# modemIO_v1.net
KiCad netlist of a schematic drawn in EAGLE
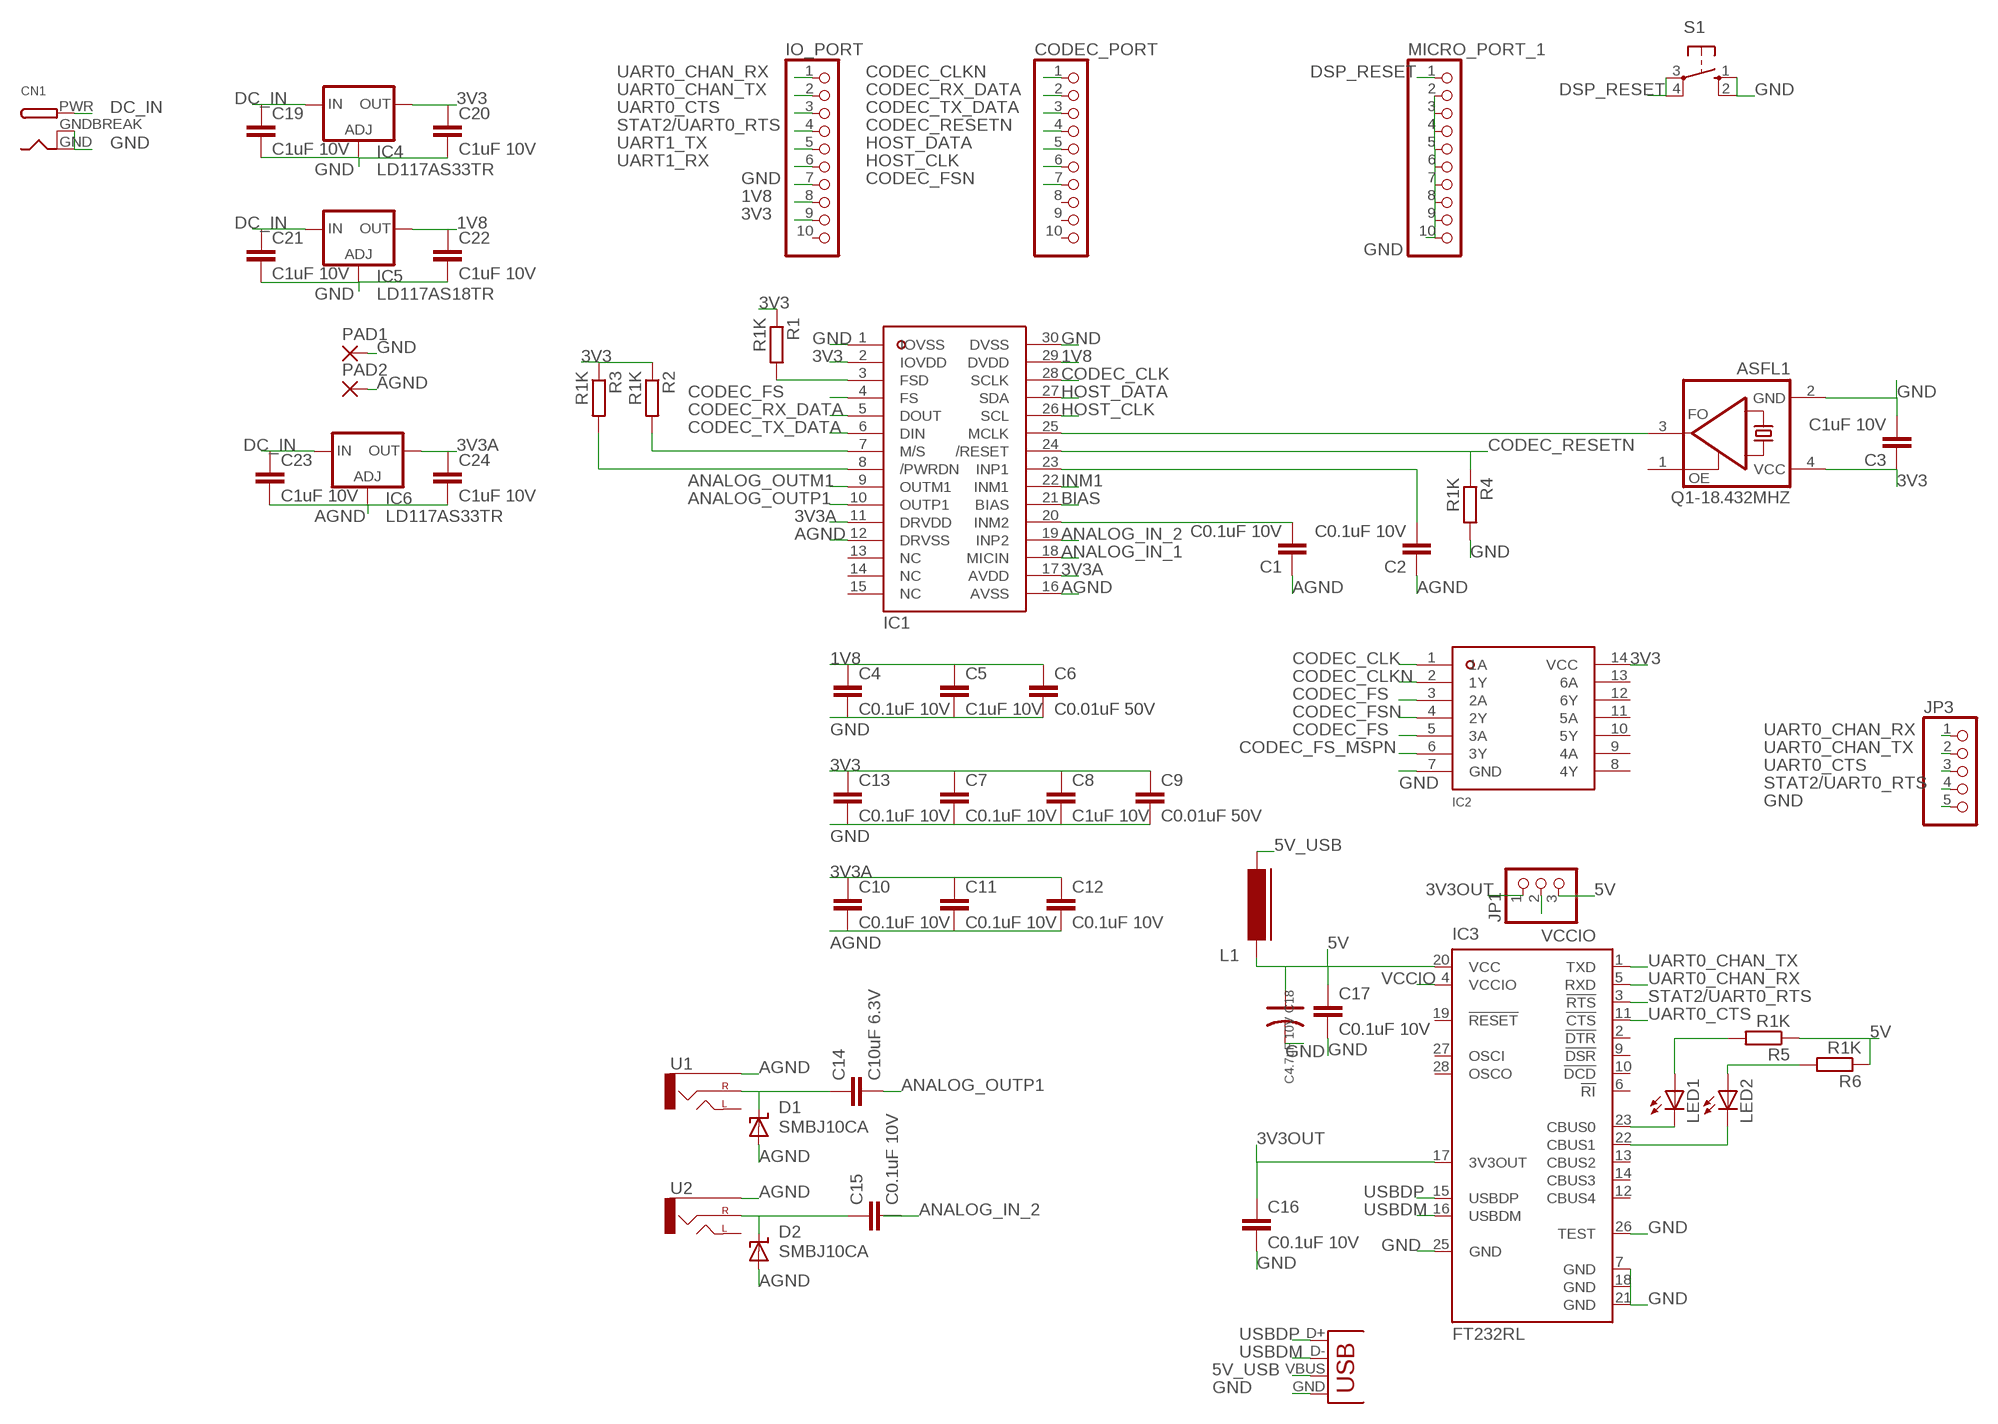
[diagram p0: schematic, sheet 1]

(export (version "E")
  (design (tool "Eeschema 10.0.6"))
  (components
    (comp (ref "C1")
      (value "C0.1uF 10V")
      (footprint "eagle-import:C0805")
      (libsource (lib "eagle-import") (part "C-EUC0805"))
    )
    (comp (ref "C2")
      (value "C0.1uF 10V")
      (footprint "eagle-import:C0805")
      (libsource (lib "eagle-import") (part "C-EUC0805"))
    )
    (comp (ref "C3")
      (value "C1uF 10V")
      (footprint "eagle-import:C0805")
      (libsource (lib "eagle-import") (part "C-EUC0805"))
    )
    (comp (ref "C4")
      (value "C0.1uF 10V")
      (footprint "eagle-import:C0805")
      (libsource (lib "eagle-import") (part "C-EUC0805"))
    )
    (comp (ref "C5")
      (value "C1uF 10V")
      (footprint "eagle-import:C0805")
      (libsource (lib "eagle-import") (part "C-EUC0805"))
    )
    (comp (ref "C6")
      (value "C0.01uF 50V")
      (footprint "eagle-import:C0805")
      (libsource (lib "eagle-import") (part "C-EUC0805"))
    )
    (comp (ref "C7")
      (value "C0.1uF 10V")
      (footprint "eagle-import:C0805")
      (libsource (lib "eagle-import") (part "C-EUC0805"))
    )
    (comp (ref "C8")
      (value "C1uF 10V")
      (footprint "eagle-import:C0805")
      (libsource (lib "eagle-import") (part "C-EUC0805"))
    )
    (comp (ref "C9")
      (value "C0.01uF 50V")
      (footprint "eagle-import:C0805")
      (libsource (lib "eagle-import") (part "C-EUC0805"))
    )
    (comp (ref "C10")
      (value "C0.1uF 10V")
      (footprint "eagle-import:C0805")
      (libsource (lib "eagle-import") (part "C-EUC0805"))
    )
    (comp (ref "C11")
      (value "C0.1uF 10V")
      (footprint "eagle-import:C0805")
      (libsource (lib "eagle-import") (part "C-EUC0805"))
    )
    (comp (ref "C12")
      (value "C0.1uF 10V")
      (footprint "eagle-import:C0805")
      (libsource (lib "eagle-import") (part "C-EUC0805"))
    )
    (comp (ref "C13")
      (value "C0.1uF 10V")
      (footprint "eagle-import:C0805")
      (libsource (lib "eagle-import") (part "C-EUC0805"))
    )
    (comp (ref "C14")
      (value "C10uF 6.3V")
      (footprint "eagle-import:C0805")
      (libsource (lib "eagle-import") (part "C-EUC0805"))
    )
    (comp (ref "C15")
      (value "C0.1uF 10V")
      (footprint "eagle-import:C0805")
      (libsource (lib "eagle-import") (part "C-EUC0805"))
    )
    (comp (ref "C16")
      (value "C0.1uF 10V")
      (footprint "eagle-import:C0805")
      (libsource (lib "eagle-import") (part "C-EUC0805"))
    )
    (comp (ref "C17")
      (value "C0.1uF 10V")
      (footprint "eagle-import:C0805")
      (libsource (lib "eagle-import") (part "C-EUC0805"))
    )
    (comp (ref "C18")
      (value "C4.7uF 10V")
      (footprint "eagle-import:AVX-C")
      (libsource (lib "eagle-import") (part "C-POLAR-C"))
    )
    (comp (ref "C19")
      (value "C1uF 10V")
      (footprint "eagle-import:C0805")
      (libsource (lib "eagle-import") (part "C-EUC0805"))
    )
    (comp (ref "C20")
      (value "C1uF 10V")
      (footprint "eagle-import:C0805")
      (libsource (lib "eagle-import") (part "C-EUC0805"))
    )
    (comp (ref "C21")
      (value "C1uF 10V")
      (footprint "eagle-import:C0805")
      (libsource (lib "eagle-import") (part "C-EUC0805"))
    )
    (comp (ref "C22")
      (value "C1uF 10V")
      (footprint "eagle-import:C0805")
      (libsource (lib "eagle-import") (part "C-EUC0805"))
    )
    (comp (ref "C23")
      (value "C1uF 10V")
      (footprint "eagle-import:C0805")
      (libsource (lib "eagle-import") (part "C-EUC0805"))
    )
    (comp (ref "C24")
      (value "C1uF 10V")
      (footprint "eagle-import:C0805")
      (libsource (lib "eagle-import") (part "C-EUC0805"))
    )
    (comp (ref "CN1")
      (value "DCBARRELPTH")
      (footprint "eagle-import:DCJACK_2MM_PTH")
      (libsource (lib "eagle-import") (part "DCBARRELPTH"))
    )
    (comp (ref "CODEC_PORT")
      (value "PINHD-1X10")
      (footprint "eagle-import:1X10")
      (libsource (lib "eagle-import") (part "PINHD-1X10"))
    )
    (comp (ref "D1")
      (value "SMBJ10CA")
      (footprint "eagle-import:SMBJ")
      (libsource (lib "eagle-import") (part "SUPPRESSOR-SMBJ"))
    )
    (comp (ref "D2")
      (value "SMBJ10CA")
      (footprint "eagle-import:SMBJ")
      (libsource (lib "eagle-import") (part "SUPPRESSOR-SMBJ"))
    )
    (comp (ref "IC1")
      (value "TLV320AIC14R-PDSO-G30")
      (footprint "eagle-import:R-PDSO-G30")
      (libsource (lib "eagle-import") (part "TLV320AIC14R-PDSO-G30"))
    )
    (comp (ref "IC2")
      (value "SN74LVC04ADRR-PDSO-G14")
      (footprint "eagle-import:R-PDSO-G14")
      (libsource (lib "eagle-import") (part "SN74LVC04ADRR-PDSO-G14"))
    )
    (comp (ref "IC3")
      (value "FT232RL")
      (footprint "eagle-import:SSOP28")
      (libsource (lib "eagle-import") (part "FT232RL"))
    )
    (comp (ref "IC4")
      (value "LD117AS33TR")
      (footprint "eagle-import:SOT223")
      (libsource (lib "eagle-import") (part "LD117A?S33TR"))
    )
    (comp (ref "IC5")
      (value "LD117AS18TR")
      (footprint "eagle-import:SOT223")
      (libsource (lib "eagle-import") (part "LD117A?S18TR"))
    )
    (comp (ref "IC6")
      (value "LD117AS33TR")
      (footprint "eagle-import:SOT223")
      (libsource (lib "eagle-import") (part "LD117A?S33TR"))
    )
    (comp (ref "IO_PORT")
      (value "PINHD-1X10")
      (footprint "eagle-import:1X10")
      (libsource (lib "eagle-import") (part "PINHD-1X10"))
    )
    (comp (ref "JP1")
      (value "PINHD-1X3")
      (footprint "eagle-import:1X03")
      (libsource (lib "eagle-import") (part "PINHD-1X3"))
    )
    (comp (ref "JP2")
      (value "USBSMD")
      (footprint "eagle-import:USB-MINIB")
      (libsource (lib "eagle-import") (part "USBSMD"))
    )
    (comp (ref "JP3")
      (value "PINHD-1X5")
      (footprint "eagle-import:1X05")
      (libsource (lib "eagle-import") (part "PINHD-1X5"))
    )
    (comp (ref "L1")
      (value "FERRITE-0603")
      (footprint "eagle-import:FB603")
      (libsource (lib "eagle-import") (part "FERRITE-0603"))
    )
    (comp (ref "LED1")
      (value "LEDCHIP-LED0805")
      (footprint "eagle-import:CHIP-LED0805")
      (libsource (lib "eagle-import") (part "LEDCHIP-LED0805"))
    )
    (comp (ref "LED2")
      (value "LEDCHIP-LED0805")
      (footprint "eagle-import:CHIP-LED0805")
      (libsource (lib "eagle-import") (part "LEDCHIP-LED0805"))
    )
    (comp (ref "MICRO_PORT_1")
      (value "PINHD-1X10")
      (footprint "eagle-import:1X10")
      (libsource (lib "eagle-import") (part "PINHD-1X10"))
    )
    (comp (ref "PAD1")
      (value "SMD2")
      (footprint "eagle-import:SMD1,27-2,54")
      (libsource (lib "eagle-import") (part "SMD2"))
    )
    (comp (ref "PAD2")
      (value "SMD2")
      (footprint "eagle-import:SMD1,27-2,54")
      (libsource (lib "eagle-import") (part "SMD2"))
    )
    (comp (ref "Q1-18.432MHZ")
      (value "ASFL1")
      (footprint "eagle-import:ASF")
      (fields (field (name "MF") "Abracon Corporation") (field (name "MPN") "ASFL1-125.000MHZ-EC-T"))
      (libsource (lib "eagle-import") (part "ASFL1"))
    )
    (comp (ref "R1")
      (value "R1K")
      (footprint "eagle-import:R0805")
      (libsource (lib "eagle-import") (part "R-EU_R0805"))
    )
    (comp (ref "R2")
      (value "R1K")
      (footprint "eagle-import:R0805")
      (libsource (lib "eagle-import") (part "R-EU_R0805"))
    )
    (comp (ref "R3")
      (value "R1K")
      (footprint "eagle-import:R0805")
      (libsource (lib "eagle-import") (part "R-EU_R0805"))
    )
    (comp (ref "R4")
      (value "R1K")
      (footprint "eagle-import:R0805")
      (libsource (lib "eagle-import") (part "R-EU_R0805"))
    )
    (comp (ref "R5")
      (value "R1K")
      (footprint "eagle-import:R0805")
      (libsource (lib "eagle-import") (part "R-EU_R0805"))
    )
    (comp (ref "R6")
      (value "R1K")
      (footprint "eagle-import:R0805")
      (libsource (lib "eagle-import") (part "R-EU_R0805"))
    )
    (comp (ref "S1")
      (value "10-XX")
      (footprint "eagle-import:B3F-10XX")
      (fields (field (name "MPN") "B3F-1000"))
      (libsource (lib "eagle-import") (part "10-XX"))
    )
    (comp (ref "U1")
      (value "AUDIO-JACKSMD2")
      (footprint "eagle-import:AUDIO-JACK-3.5MM-SMD")
      (libsource (lib "eagle-import") (part "AUDIO-JACKSMD2"))
    )
    (comp (ref "U2")
      (value "AUDIO-JACKSMD2")
      (footprint "eagle-import:AUDIO-JACK-3.5MM-SMD")
      (libsource (lib "eagle-import") (part "AUDIO-JACKSMD2"))
    )
  )
  (nets
    (net (code "1") (name "/1V8") (class "Default")
      (node (ref "C22") (pin "1") (pinfunction "1_1") (pintype "passive"))
      (node (ref "C4") (pin "1") (pinfunction "1_1") (pintype "passive"))
      (node (ref "C5") (pin "1") (pinfunction "1_1") (pintype "passive"))
      (node (ref "C6") (pin "1") (pinfunction "1_1") (pintype "passive"))
      (node (ref "IC1") (pin "29") (pinfunction "DVDD_29") (pintype "bidirectional"))
      (node (ref "IC5") (pin "4") (pinfunction "OUT_4") (pintype "passive"))
      (node (ref "IO_PORT") (pin "8") (pinfunction "8_8") (pintype "passive"))
    )
    (net (code "2") (name "/3V3") (class "Default")
      (node (ref "C13") (pin "1") (pinfunction "1_1") (pintype "passive"))
      (node (ref "C20") (pin "1") (pinfunction "1_1") (pintype "passive"))
      (node (ref "C3") (pin "1") (pinfunction "1_1") (pintype "passive"))
      (node (ref "C7") (pin "1") (pinfunction "1_1") (pintype "passive"))
      (node (ref "C8") (pin "1") (pinfunction "1_1") (pintype "passive"))
      (node (ref "C9") (pin "1") (pinfunction "1_1") (pintype "passive"))
      (node (ref "IC1") (pin "2") (pinfunction "IOVDD_2") (pintype "bidirectional"))
      (node (ref "IC2") (pin "14") (pinfunction "VCC_14") (pintype "bidirectional"))
      (node (ref "IC4") (pin "4") (pinfunction "OUT_4") (pintype "passive"))
      (node (ref "IO_PORT") (pin "9") (pinfunction "9_9") (pintype "passive"))
      (node (ref "Q1-18.432MHZ") (pin "4") (pinfunction "VCC_4") (pintype "power_in"))
      (node (ref "R1") (pin "1") (pinfunction "1_1") (pintype "passive"))
      (node (ref "R2") (pin "1") (pinfunction "1_1") (pintype "passive"))
      (node (ref "R3") (pin "1") (pinfunction "1_1") (pintype "passive"))
    )
    (net (code "3") (name "/3V3A") (class "Default")
      (node (ref "C10") (pin "1") (pinfunction "1_1") (pintype "passive"))
      (node (ref "C11") (pin "1") (pinfunction "1_1") (pintype "passive"))
      (node (ref "C12") (pin "1") (pinfunction "1_1") (pintype "passive"))
      (node (ref "C24") (pin "1") (pinfunction "1_1") (pintype "passive"))
      (node (ref "IC1") (pin "11") (pinfunction "DRVDD_11") (pintype "bidirectional"))
      (node (ref "IC1") (pin "17") (pinfunction "AVDD_17") (pintype "bidirectional"))
      (node (ref "IC6") (pin "4") (pinfunction "OUT_4") (pintype "passive"))
    )
    (net (code "4") (name "/3V3OUT") (class "Default")
      (node (ref "C16") (pin "1") (pinfunction "1_1") (pintype "passive"))
      (node (ref "IC3") (pin "17") (pinfunction "3V3OUT_17") (pintype "output"))
      (node (ref "JP1") (pin "1") (pinfunction "1_1") (pintype "passive"))
    )
    (net (code "5") (name "/5V") (class "Default")
      (node (ref "C17") (pin "1") (pinfunction "1_1") (pintype "passive"))
      (node (ref "C18") (pin "+") (pinfunction "1_+") (pintype "bidirectional"))
      (node (ref "IC3") (pin "20") (pinfunction "VCC_20") (pintype "power_in"))
      (node (ref "JP1") (pin "3") (pinfunction "3_3") (pintype "passive"))
      (node (ref "L1") (pin "1") (pinfunction "1_1") (pintype "passive"))
      (node (ref "R5") (pin "1") (pinfunction "1_1") (pintype "passive"))
      (node (ref "R6") (pin "1") (pinfunction "1_1") (pintype "passive"))
    )
    (net (code "6") (name "/5V_USB") (class "Default")
      (node (ref "JP2") (pin "VBUS") (pinfunction "VBUS_VBUS") (pintype "bidirectional"))
      (node (ref "L1") (pin "2") (pinfunction "2_2") (pintype "passive"))
    )
    (net (code "7") (name "/AGND") (class "Default")
      (node (ref "C1") (pin "1") (pinfunction "1_1") (pintype "passive"))
      (node (ref "C10") (pin "2") (pinfunction "2_2") (pintype "passive"))
      (node (ref "C11") (pin "2") (pinfunction "2_2") (pintype "passive"))
      (node (ref "C12") (pin "2") (pinfunction "2_2") (pintype "passive"))
      (node (ref "C2") (pin "1") (pinfunction "1_1") (pintype "passive"))
      (node (ref "C23") (pin "2") (pinfunction "2_2") (pintype "passive"))
      (node (ref "C24") (pin "2") (pinfunction "2_2") (pintype "passive"))
      (node (ref "D1") (pin "A") (pinfunction "A_A") (pintype "passive"))
      (node (ref "D2") (pin "A") (pinfunction "A_A") (pintype "passive"))
      (node (ref "IC1") (pin "12") (pinfunction "DRVSS_12") (pintype "bidirectional"))
      (node (ref "IC1") (pin "16") (pinfunction "AVSS_16") (pintype "bidirectional"))
      (node (ref "IC6") (pin "1") (pinfunction "ADJ_1") (pintype "input"))
      (node (ref "PAD2") (pin "1") (pinfunction "P_1") (pintype "passive"))
      (node (ref "U1") (pin "SLEEVE") (pinfunction "SLEEVE_SLEEVE") (pintype "bidirectional"))
      (node (ref "U2") (pin "SLEEVE") (pinfunction "SLEEVE_SLEEVE") (pintype "bidirectional"))
    )
    (net (code "8") (name "/ANALOG_IN_1") (class "Default")
      (node (ref "IC1") (pin "18") (pinfunction "MICIN_18") (pintype "bidirectional"))
    )
    (net (code "9") (name "/ANALOG_IN_2") (class "Default")
      (node (ref "C15") (pin "2") (pinfunction "2_2") (pintype "passive"))
      (node (ref "IC1") (pin "19") (pinfunction "INP2_19") (pintype "bidirectional"))
    )
    (net (code "10") (name "/ANALOG_OUTM1") (class "Default")
      (node (ref "IC1") (pin "9") (pinfunction "OUTM1_9") (pintype "bidirectional"))
    )
    (net (code "11") (name "/ANALOG_OUTP1") (class "Default")
      (node (ref "C14") (pin "2") (pinfunction "2_2") (pintype "passive"))
      (node (ref "IC1") (pin "10") (pinfunction "OUTP1_10") (pintype "bidirectional"))
    )
    (net (code "12") (name "/BIAS") (class "Default")
      (node (ref "IC1") (pin "21") (pinfunction "BIAS_21") (pintype "bidirectional"))
    )
    (net (code "13") (name "/CODEC_CLK") (class "Default")
      (node (ref "IC1") (pin "28") (pinfunction "SCLK_28") (pintype "bidirectional"))
      (node (ref "IC2") (pin "1") (pinfunction "1A_1") (pintype "bidirectional"))
    )
    (net (code "14") (name "/CODEC_CLKN") (class "Default")
      (node (ref "CODEC_PORT") (pin "1") (pinfunction "1_1") (pintype "passive"))
      (node (ref "IC2") (pin "2") (pinfunction "1Y_2") (pintype "bidirectional"))
    )
    (net (code "15") (name "/CODEC_FS") (class "Default")
      (node (ref "IC1") (pin "4") (pinfunction "FS_4") (pintype "bidirectional"))
      (node (ref "IC2") (pin "3") (pinfunction "2A_3") (pintype "bidirectional"))
      (node (ref "IC2") (pin "5") (pinfunction "3A_5") (pintype "bidirectional"))
    )
    (net (code "16") (name "/CODEC_FSN") (class "Default")
      (node (ref "CODEC_PORT") (pin "7") (pinfunction "7_7") (pintype "passive"))
      (node (ref "IC2") (pin "4") (pinfunction "2Y_4") (pintype "bidirectional"))
    )
    (net (code "17") (name "/CODEC_FS_MSPN") (class "Default")
      (node (ref "IC2") (pin "6") (pinfunction "3Y_6") (pintype "bidirectional"))
    )
    (net (code "18") (name "/CODEC_RESETN") (class "Default")
      (node (ref "CODEC_PORT") (pin "4") (pinfunction "4_4") (pintype "passive"))
      (node (ref "IC1") (pin "24") (pinfunction "/RESET_24") (pintype "bidirectional"))
      (node (ref "R4") (pin "1") (pinfunction "1_1") (pintype "passive"))
    )
    (net (code "19") (name "/CODEC_RX_DATA") (class "Default")
      (node (ref "CODEC_PORT") (pin "2") (pinfunction "2_2") (pintype "passive"))
      (node (ref "IC1") (pin "5") (pinfunction "DOUT_5") (pintype "bidirectional"))
    )
    (net (code "20") (name "/CODEC_TX_DATA") (class "Default")
      (node (ref "CODEC_PORT") (pin "3") (pinfunction "3_3") (pintype "passive"))
      (node (ref "IC1") (pin "6") (pinfunction "DIN_6") (pintype "bidirectional"))
    )
    (net (code "21") (name "/DC_IN") (class "Default")
      (node (ref "C19") (pin "1") (pinfunction "1_1") (pintype "passive"))
      (node (ref "C21") (pin "1") (pinfunction "1_1") (pintype "passive"))
      (node (ref "C23") (pin "1") (pinfunction "1_1") (pintype "passive"))
      (node (ref "CN1") (pin "PWR") (pinfunction "PWR_PWR") (pintype "power_in"))
      (node (ref "IC4") (pin "3") (pinfunction "IN_3") (pintype "input"))
      (node (ref "IC5") (pin "3") (pinfunction "IN_3") (pintype "input"))
      (node (ref "IC6") (pin "3") (pinfunction "IN_3") (pintype "input"))
    )
    (net (code "22") (name "/DSP_RESET") (class "Default")
      (node (ref "MICRO_PORT_1") (pin "1") (pinfunction "1_1") (pintype "passive"))
      (node (ref "S1") (pin "3") (pinfunction "P_3") (pintype "passive"))
      (node (ref "S1") (pin "4") (pinfunction "P1_4") (pintype "passive"))
    )
    (net (code "23") (name "/GND") (class "Default")
      (node (ref "C13") (pin "2") (pinfunction "2_2") (pintype "passive"))
      (node (ref "C16") (pin "2") (pinfunction "2_2") (pintype "passive"))
      (node (ref "C17") (pin "2") (pinfunction "2_2") (pintype "passive"))
      (node (ref "C18") (pin "-") (pinfunction "2_-") (pintype "bidirectional"))
      (node (ref "C19") (pin "2") (pinfunction "2_2") (pintype "passive"))
      (node (ref "C20") (pin "2") (pinfunction "2_2") (pintype "passive"))
      (node (ref "C21") (pin "2") (pinfunction "2_2") (pintype "passive"))
      (node (ref "C22") (pin "2") (pinfunction "2_2") (pintype "passive"))
      (node (ref "C3") (pin "2") (pinfunction "2_2") (pintype "passive"))
      (node (ref "C4") (pin "2") (pinfunction "2_2") (pintype "passive"))
      (node (ref "C5") (pin "2") (pinfunction "2_2") (pintype "passive"))
      (node (ref "C6") (pin "2") (pinfunction "2_2") (pintype "passive"))
      (node (ref "C7") (pin "2") (pinfunction "2_2") (pintype "passive"))
      (node (ref "C8") (pin "2") (pinfunction "2_2") (pintype "passive"))
      (node (ref "C9") (pin "2") (pinfunction "2_2") (pintype "passive"))
      (node (ref "CN1") (pin "GND") (pinfunction "GND_GND") (pintype "power_in"))
      (node (ref "CN1") (pin "GNDBREAK") (pinfunction "GNDBREAK_GNDBREAK") (pintype "power_in"))
      (node (ref "IC1") (pin "1") (pinfunction "IOVSS_1") (pintype "bidirectional"))
      (node (ref "IC1") (pin "30") (pinfunction "DVSS_30") (pintype "bidirectional"))
      (node (ref "IC2") (pin "7") (pinfunction "GND_7") (pintype "bidirectional"))
      (node (ref "IC3") (pin "18") (pinfunction "GND_18") (pintype "power_in"))
      (node (ref "IC3") (pin "21") (pinfunction "GND_21") (pintype "power_in"))
      (node (ref "IC3") (pin "25") (pinfunction "GND_25") (pintype "power_in"))
      (node (ref "IC3") (pin "26") (pinfunction "TEST_26") (pintype "input"))
      (node (ref "IC3") (pin "7") (pinfunction "GND_7") (pintype "power_in"))
      (node (ref "IC4") (pin "1") (pinfunction "ADJ_1") (pintype "input"))
      (node (ref "IC5") (pin "1") (pinfunction "ADJ_1") (pintype "input"))
      (node (ref "IO_PORT") (pin "7") (pinfunction "7_7") (pintype "passive"))
      (node (ref "JP2") (pin "GND") (pinfunction "GND_GND") (pintype "bidirectional"))
      (node (ref "JP3") (pin "5") (pinfunction "5_5") (pintype "passive"))
      (node (ref "MICRO_PORT_1") (pin "10") (pinfunction "10_10") (pintype "passive"))
      (node (ref "MICRO_PORT_1") (pin "2") (pinfunction "2_2") (pintype "passive"))
      (node (ref "MICRO_PORT_1") (pin "3") (pinfunction "3_3") (pintype "passive"))
      (node (ref "MICRO_PORT_1") (pin "4") (pinfunction "4_4") (pintype "passive"))
      (node (ref "MICRO_PORT_1") (pin "5") (pinfunction "5_5") (pintype "passive"))
      (node (ref "MICRO_PORT_1") (pin "6") (pinfunction "6_6") (pintype "passive"))
      (node (ref "MICRO_PORT_1") (pin "7") (pinfunction "7_7") (pintype "passive"))
      (node (ref "MICRO_PORT_1") (pin "8") (pinfunction "8_8") (pintype "passive"))
      (node (ref "MICRO_PORT_1") (pin "9") (pinfunction "9_9") (pintype "passive"))
      (node (ref "PAD1") (pin "1") (pinfunction "P_1") (pintype "passive"))
      (node (ref "Q1-18.432MHZ") (pin "2") (pinfunction "GND_2") (pintype "power_in"))
      (node (ref "R4") (pin "2") (pinfunction "2_2") (pintype "passive"))
      (node (ref "S1") (pin "1") (pinfunction "S_1") (pintype "passive"))
      (node (ref "S1") (pin "2") (pinfunction "S1_2") (pintype "passive"))
    )
    (net (code "24") (name "/HOST_CLK") (class "Default")
      (node (ref "CODEC_PORT") (pin "6") (pinfunction "6_6") (pintype "passive"))
      (node (ref "IC1") (pin "26") (pinfunction "SCL_26") (pintype "bidirectional"))
    )
    (net (code "25") (name "/HOST_DATA") (class "Default")
      (node (ref "CODEC_PORT") (pin "5") (pinfunction "5_5") (pintype "passive"))
      (node (ref "IC1") (pin "27") (pinfunction "SDA_27") (pintype "bidirectional"))
    )
    (net (code "26") (name "/INM1") (class "Default")
      (node (ref "IC1") (pin "22") (pinfunction "INM1_22") (pintype "bidirectional"))
    )
    (net (code "27") (name "/STAT2{slash}UART0_RTS") (class "Default")
      (node (ref "IC3") (pin "3") (pinfunction "~{RTS}_3") (pintype "output"))
      (node (ref "IO_PORT") (pin "4") (pinfunction "4_4") (pintype "passive"))
      (node (ref "JP3") (pin "4") (pinfunction "4_4") (pintype "passive"))
    )
    (net (code "28") (name "/UART0_CHAN_RX") (class "Default")
      (node (ref "IC3") (pin "5") (pinfunction "RXD_5") (pintype "input"))
      (node (ref "IO_PORT") (pin "1") (pinfunction "1_1") (pintype "passive"))
      (node (ref "JP3") (pin "1") (pinfunction "1_1") (pintype "passive"))
    )
    (net (code "29") (name "/UART0_CHAN_TX") (class "Default")
      (node (ref "IC3") (pin "1") (pinfunction "TXD_1") (pintype "output"))
      (node (ref "IO_PORT") (pin "2") (pinfunction "2_2") (pintype "passive"))
      (node (ref "JP3") (pin "2") (pinfunction "2_2") (pintype "passive"))
    )
    (net (code "30") (name "/UART0_CTS") (class "Default")
      (node (ref "IC3") (pin "11") (pinfunction "~{CTS}_11") (pintype "input"))
      (node (ref "IO_PORT") (pin "3") (pinfunction "3_3") (pintype "passive"))
      (node (ref "JP3") (pin "3") (pinfunction "3_3") (pintype "passive"))
    )
    (net (code "31") (name "/UART1_RX") (class "Default")
      (node (ref "IO_PORT") (pin "6") (pinfunction "6_6") (pintype "passive"))
    )
    (net (code "32") (name "/UART1_TX") (class "Default")
      (node (ref "IO_PORT") (pin "5") (pinfunction "5_5") (pintype "passive"))
    )
    (net (code "33") (name "/USBDM") (class "Default")
      (node (ref "IC3") (pin "16") (pinfunction "USBDM_16") (pintype "bidirectional"))
      (node (ref "JP2") (pin "D-") (pinfunction "D-_D-") (pintype "bidirectional"))
    )
    (net (code "34") (name "/USBDP") (class "Default")
      (node (ref "IC3") (pin "15") (pinfunction "USBDP_15") (pintype "bidirectional"))
      (node (ref "JP2") (pin "D+") (pinfunction "D+_D+") (pintype "bidirectional"))
    )
    (net (code "35") (name "/VCCIO") (class "Default")
      (node (ref "IC3") (pin "4") (pinfunction "VCCIO_4") (pintype "power_in"))
      (node (ref "JP1") (pin "2") (pinfunction "2_2") (pintype "passive"))
    )
    (net (code "36") (name "Net-(IC1-FSD)") (class "Default")
      (node (ref "IC1") (pin "3") (pinfunction "FSD_3") (pintype "bidirectional"))
      (node (ref "R1") (pin "2") (pinfunction "2_2") (pintype "passive"))
    )
    (net (code "37") (name "Net-(IC1-INM2)") (class "Default")
      (node (ref "C1") (pin "2") (pinfunction "2_2") (pintype "passive"))
      (node (ref "IC1") (pin "20") (pinfunction "INM2_20") (pintype "bidirectional"))
    )
    (net (code "38") (name "Net-(IC1-INP1)") (class "Default")
      (node (ref "C2") (pin "2") (pinfunction "2_2") (pintype "passive"))
      (node (ref "IC1") (pin "23") (pinfunction "INP1_23") (pintype "bidirectional"))
    )
    (net (code "39") (name "Net-(IC1-MCLK)") (class "Default")
      (node (ref "IC1") (pin "25") (pinfunction "MCLK_25") (pintype "bidirectional"))
      (node (ref "Q1-18.432MHZ") (pin "3") (pinfunction "FO_3") (pintype "output"))
    )
    (net (code "40") (name "Net-(IC1-M{slash}S)") (class "Default")
      (node (ref "IC1") (pin "7") (pinfunction "M/S_7") (pintype "bidirectional"))
      (node (ref "R2") (pin "2") (pinfunction "2_2") (pintype "passive"))
    )
    (net (code "41") (name "Net-(IC1-{slash}PWRDN)") (class "Default")
      (node (ref "IC1") (pin "8") (pinfunction "/PWRDN_8") (pintype "bidirectional"))
      (node (ref "R3") (pin "2") (pinfunction "2_2") (pintype "passive"))
    )
    (net (code "42") (name "Net-(IC3-CBUS0)") (class "Default")
      (node (ref "IC3") (pin "23") (pinfunction "CBUS0_23") (pintype "bidirectional"))
      (node (ref "LED1") (pin "C") (pinfunction "C_C") (pintype "passive"))
    )
    (net (code "43") (name "Net-(IC3-CBUS1)") (class "Default")
      (node (ref "IC3") (pin "22") (pinfunction "CBUS1_22") (pintype "bidirectional"))
      (node (ref "LED2") (pin "C") (pinfunction "C_C") (pintype "passive"))
    )
    (net (code "44") (name "Net-(LED1-PadA)") (class "Default")
      (node (ref "LED1") (pin "A") (pinfunction "A_A") (pintype "passive"))
      (node (ref "R5") (pin "2") (pinfunction "2_2") (pintype "passive"))
    )
    (net (code "45") (name "Net-(LED2-PadA)") (class "Default")
      (node (ref "LED2") (pin "A") (pinfunction "A_A") (pintype "passive"))
      (node (ref "R6") (pin "2") (pinfunction "2_2") (pintype "passive"))
    )
    (net (code "46") (name "Net-(U1-RIGHT)") (class "Default")
      (node (ref "C14") (pin "1") (pinfunction "1_1") (pintype "passive"))
      (node (ref "D1") (pin "C") (pinfunction "C_C") (pintype "passive"))
      (node (ref "U1") (pin "RING") (pinfunction "RIGHT_RING") (pintype "bidirectional"))
    )
    (net (code "47") (name "Net-(U2-RIGHT)") (class "Default")
      (node (ref "C15") (pin "1") (pinfunction "1_1") (pintype "passive"))
      (node (ref "D2") (pin "C") (pinfunction "C_C") (pintype "passive"))
      (node (ref "U2") (pin "RING") (pinfunction "RIGHT_RING") (pintype "bidirectional"))
    )
    (net (code "48") (name "unconnected-(CODEC_PORT-Pad8)") (class "Default")
      (node (ref "CODEC_PORT") (pin "8") (pinfunction "8_8") (pintype "passive"))
    )
    (net (code "49") (name "unconnected-(CODEC_PORT-Pad9)") (class "Default")
      (node (ref "CODEC_PORT") (pin "9") (pinfunction "9_9") (pintype "passive"))
    )
    (net (code "50") (name "unconnected-(CODEC_PORT-Pad10)") (class "Default")
      (node (ref "CODEC_PORT") (pin "10") (pinfunction "10_10") (pintype "passive"))
    )
    (net (code "51") (name "unconnected-(IC1-NC-Pad13)") (class "Default")
      (node (ref "IC1") (pin "13") (pinfunction "NC_13") (pintype "bidirectional"))
    )
    (net (code "52") (name "unconnected-(IC1-NC-Pad14)") (class "Default")
      (node (ref "IC1") (pin "14") (pinfunction "NC_14") (pintype "bidirectional"))
    )
    (net (code "53") (name "unconnected-(IC1-NC-Pad15)") (class "Default")
      (node (ref "IC1") (pin "15") (pinfunction "NC_15") (pintype "bidirectional"))
    )
    (net (code "54") (name "unconnected-(IC2-4A-Pad9)") (class "Default")
      (node (ref "IC2") (pin "9") (pinfunction "4A_9") (pintype "bidirectional"))
    )
    (net (code "55") (name "unconnected-(IC2-4Y-Pad8)") (class "Default")
      (node (ref "IC2") (pin "8") (pinfunction "4Y_8") (pintype "bidirectional"))
    )
    (net (code "56") (name "unconnected-(IC2-5A-Pad11)") (class "Default")
      (node (ref "IC2") (pin "11") (pinfunction "5A_11") (pintype "bidirectional"))
    )
    (net (code "57") (name "unconnected-(IC2-5Y-Pad10)") (class "Default")
      (node (ref "IC2") (pin "10") (pinfunction "5Y_10") (pintype "bidirectional"))
    )
    (net (code "58") (name "unconnected-(IC2-6A-Pad13)") (class "Default")
      (node (ref "IC2") (pin "13") (pinfunction "6A_13") (pintype "bidirectional"))
    )
    (net (code "59") (name "unconnected-(IC2-6Y-Pad12)") (class "Default")
      (node (ref "IC2") (pin "12") (pinfunction "6Y_12") (pintype "bidirectional"))
    )
    (net (code "60") (name "unconnected-(IC3-CBUS2-Pad13)") (class "Default")
      (node (ref "IC3") (pin "13") (pinfunction "CBUS2_13") (pintype "bidirectional"))
    )
    (net (code "61") (name "unconnected-(IC3-CBUS3-Pad14)") (class "Default")
      (node (ref "IC3") (pin "14") (pinfunction "CBUS3_14") (pintype "bidirectional"))
    )
    (net (code "62") (name "unconnected-(IC3-CBUS4-Pad12)") (class "Default")
      (node (ref "IC3") (pin "12") (pinfunction "CBUS4_12") (pintype "bidirectional"))
    )
    (net (code "63") (name "unconnected-(IC3-OSCI-Pad27)") (class "Default")
      (node (ref "IC3") (pin "27") (pinfunction "OSCI_27") (pintype "input"))
    )
    (net (code "64") (name "unconnected-(IC3-OSCO-Pad28)") (class "Default")
      (node (ref "IC3") (pin "28") (pinfunction "OSCO_28") (pintype "output"))
    )
    (net (code "65") (name "unconnected-(IC3-~{DCD}-Pad10)") (class "Default")
      (node (ref "IC3") (pin "10") (pinfunction "~{DCD}_10") (pintype "input"))
    )
    (net (code "66") (name "unconnected-(IC3-~{DSR}-Pad9)") (class "Default")
      (node (ref "IC3") (pin "9") (pinfunction "~{DSR}_9") (pintype "input"))
    )
    (net (code "67") (name "unconnected-(IC3-~{DTR}-Pad2)") (class "Default")
      (node (ref "IC3") (pin "2") (pinfunction "~{DTR}_2") (pintype "output"))
    )
    (net (code "68") (name "unconnected-(IC3-~{RESET}-Pad19)") (class "Default")
      (node (ref "IC3") (pin "19") (pinfunction "~{RESET}_19") (pintype "input"))
    )
    (net (code "69") (name "unconnected-(IC3-~{RI}-Pad6)") (class "Default")
      (node (ref "IC3") (pin "6") (pinfunction "~{RI}_6") (pintype "input"))
    )
    (net (code "70") (name "unconnected-(IO_PORT-Pad10)") (class "Default")
      (node (ref "IO_PORT") (pin "10") (pinfunction "10_10") (pintype "passive"))
    )
    (net (code "71") (name "unconnected-(Q1-18.432MHZ-OE-Pad1)") (class "Default")
      (node (ref "Q1-18.432MHZ") (pin "1") (pinfunction "OE_1") (pintype "input"))
    )
    (net (code "72") (name "unconnected-(U1-LEFT-PadTIP)") (class "Default")
      (node (ref "U1") (pin "TIP") (pinfunction "LEFT_TIP") (pintype "bidirectional"))
    )
    (net (code "73") (name "unconnected-(U2-LEFT-PadTIP)") (class "Default")
      (node (ref "U2") (pin "TIP") (pinfunction "LEFT_TIP") (pintype "bidirectional"))
    )
  )
)
